# 2312_RFID.net
KiCad netlist of a schematic drawn in Altium Designer
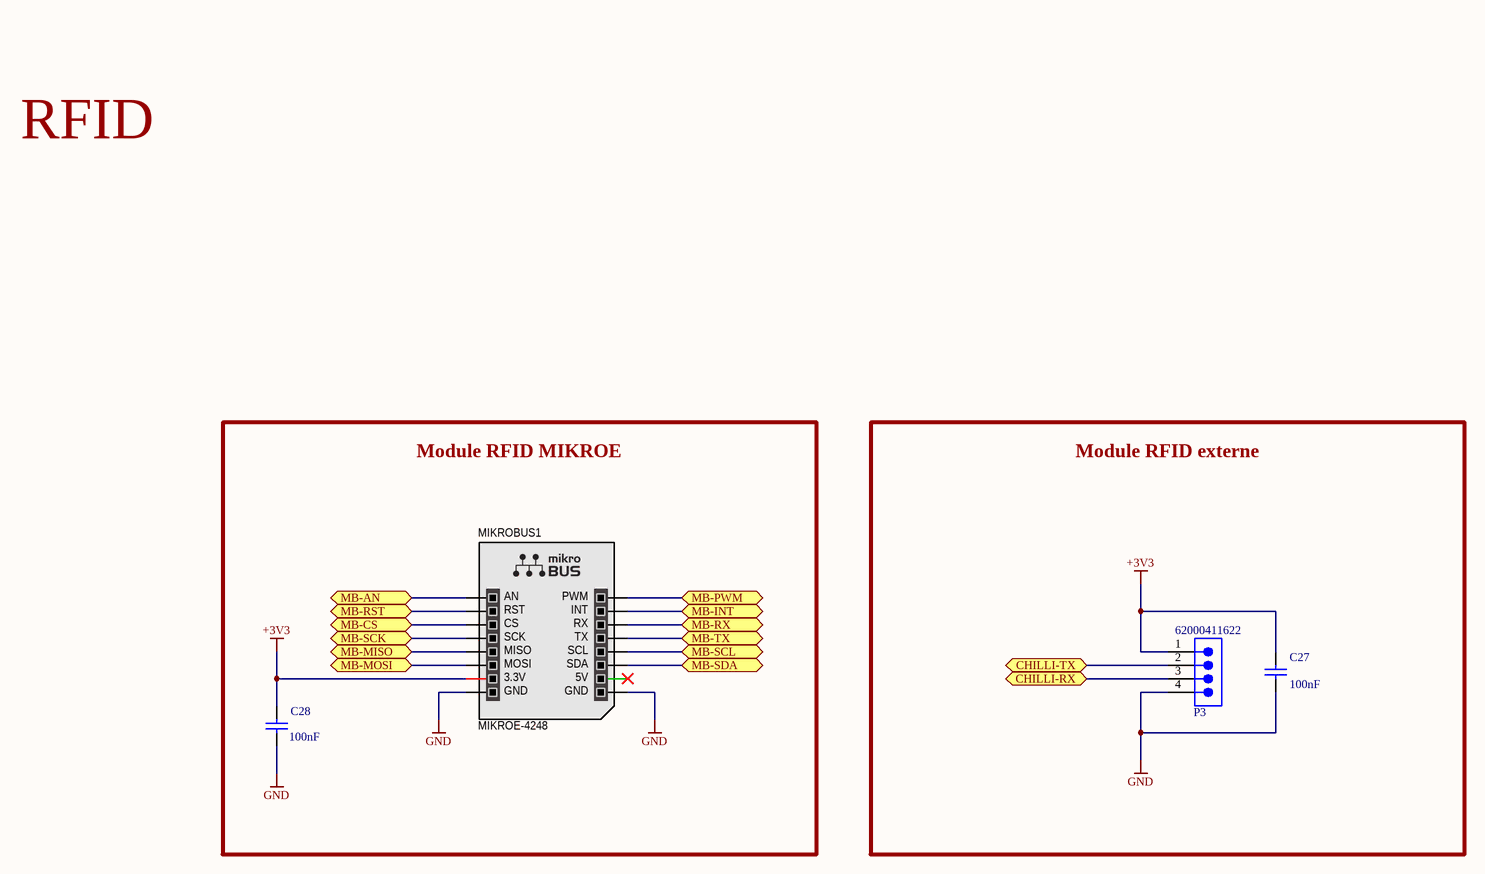
[diagram p0: 2312_RFID.SchDoc]

(export (version "E")
  (design (tool "Eeschema 10.0.6"))
  (components
    (comp (ref "C27")
      (value "885012207016")
      (footprint "WCAP-CSGP_0805_L2W1.25H0.8_Reflow")
      (description "WCAP-CSGP Multilayer Ceramic Chip Capacitor, General Purpose, size 0805, X7R, 100nF, 10VDC")
      (fields (field (name "MANUFACTURER") "Wurth Elektronik") (field (name "CAPACITANCE") "100nF"))
      (libsource (lib "WCAP-CSGP") (part "885012207016"))
    )
    (comp (ref "C28")
      (value "885012207016")
      (footprint "WCAP-CSGP_0805_L2W1.25H0.8_Reflow")
      (description "WCAP-CSGP Multilayer Ceramic Chip Capacitor, General Purpose, size 0805, X7R, 100nF, 10VDC")
      (fields (field (name "MANUFACTURER") "Wurth Elektronik") (field (name "CAPACITANCE") "100nF"))
      (libsource (lib "WCAP-CSGP") (part "885012207016"))
    )
    (comp (ref "MIKROBUS1")
      (value "MIKROE-4248")
      (footprint "MIKROBUS HOST SMD 16 - Black")
      (description "mikroBUS socket")
      (libsource (lib "SOCKET mikroBUS 16 SMD") (part "MIKROBUS HOST CONN"))
    )
    (comp (ref "P3")
      (value "62000411622")
      (footprint "62000411622")
      (description "WR-WTB Male Vertical Shrouded Header, pitch 2mm, 4pins")
      (fields (field (name "MANUFACTURER") "Wurth Elektronik"))
      (libsource (lib "WR-WTB") (part "62000411622"))
    )
  )
  (nets
    (net (code "1") (name "+3V3") (class "Default")
      (node (ref "C27") (pin "2") (pinfunction "2_2") (pintype "passive"))
      (node (ref "C28") (pin "2") (pinfunction "2_2") (pintype "passive"))
      (node (ref "MIKROBUS1") (pin "7") (pinfunction "3.3V_7") (pintype "passive"))
      (node (ref "P3") (pin "1") (pinfunction "1_1") (pintype "passive"))
    )
    (net (code "2") (name "/CHILLI-RX") (class "Default")
      (node (ref "P3") (pin "3") (pinfunction "3_3") (pintype "passive"))
    )
    (net (code "3") (name "/CHILLI-TX") (class "Default")
      (node (ref "P3") (pin "2") (pinfunction "2_2") (pintype "passive"))
    )
    (net (code "4") (name "/MB-AN") (class "Default")
      (node (ref "MIKROBUS1") (pin "1") (pinfunction "AN_1") (pintype "passive"))
    )
    (net (code "5") (name "/MB-CS") (class "Default")
      (node (ref "MIKROBUS1") (pin "3") (pinfunction "CS_3") (pintype "passive"))
    )
    (net (code "6") (name "/MB-INT") (class "Default")
      (node (ref "MIKROBUS1") (pin "15") (pinfunction "INT_15") (pintype "passive"))
    )
    (net (code "7") (name "/MB-MISO") (class "Default")
      (node (ref "MIKROBUS1") (pin "5") (pinfunction "MISO_5") (pintype "passive"))
    )
    (net (code "8") (name "/MB-MOSI") (class "Default")
      (node (ref "MIKROBUS1") (pin "6") (pinfunction "MOSI_6") (pintype "passive"))
    )
    (net (code "9") (name "/MB-PWM") (class "Default")
      (node (ref "MIKROBUS1") (pin "16") (pinfunction "PWM_16") (pintype "passive"))
    )
    (net (code "10") (name "/MB-RST") (class "Default")
      (node (ref "MIKROBUS1") (pin "2") (pinfunction "RST_2") (pintype "passive"))
    )
    (net (code "11") (name "/MB-RX") (class "Default")
      (node (ref "MIKROBUS1") (pin "14") (pinfunction "RX_14") (pintype "passive"))
    )
    (net (code "12") (name "/MB-SCK") (class "Default")
      (node (ref "MIKROBUS1") (pin "4") (pinfunction "SCK_4") (pintype "passive"))
    )
    (net (code "13") (name "/MB-SCL") (class "Default")
      (node (ref "MIKROBUS1") (pin "12") (pinfunction "SCL_12") (pintype "passive"))
    )
    (net (code "14") (name "/MB-SDA") (class "Default")
      (node (ref "MIKROBUS1") (pin "11") (pinfunction "SDA_11") (pintype "passive"))
    )
    (net (code "15") (name "/MB-TX") (class "Default")
      (node (ref "MIKROBUS1") (pin "13") (pinfunction "TX_13") (pintype "passive"))
    )
    (net (code "16") (name "GND") (class "Default")
      (node (ref "C27") (pin "1") (pinfunction "1_1") (pintype "passive"))
      (node (ref "C28") (pin "1") (pinfunction "1_1") (pintype "passive"))
      (node (ref "MIKROBUS1") (pin "8") (pinfunction "GND_8") (pintype "passive"))
      (node (ref "MIKROBUS1") (pin "9") (pinfunction "GND_9") (pintype "passive"))
      (node (ref "P3") (pin "4") (pinfunction "4_4") (pintype "passive"))
    )
    (net (code "17") (name "unconnected-(MIKROBUS1-5V-Pad10)") (class "Default")
      (node (ref "MIKROBUS1") (pin "10") (pinfunction "5V_10") (pintype "passive+no_connect"))
    )
  )
)
